# Custom_Board_2_Final.net
KiCad netlist of a schematic drawn in EAGLE
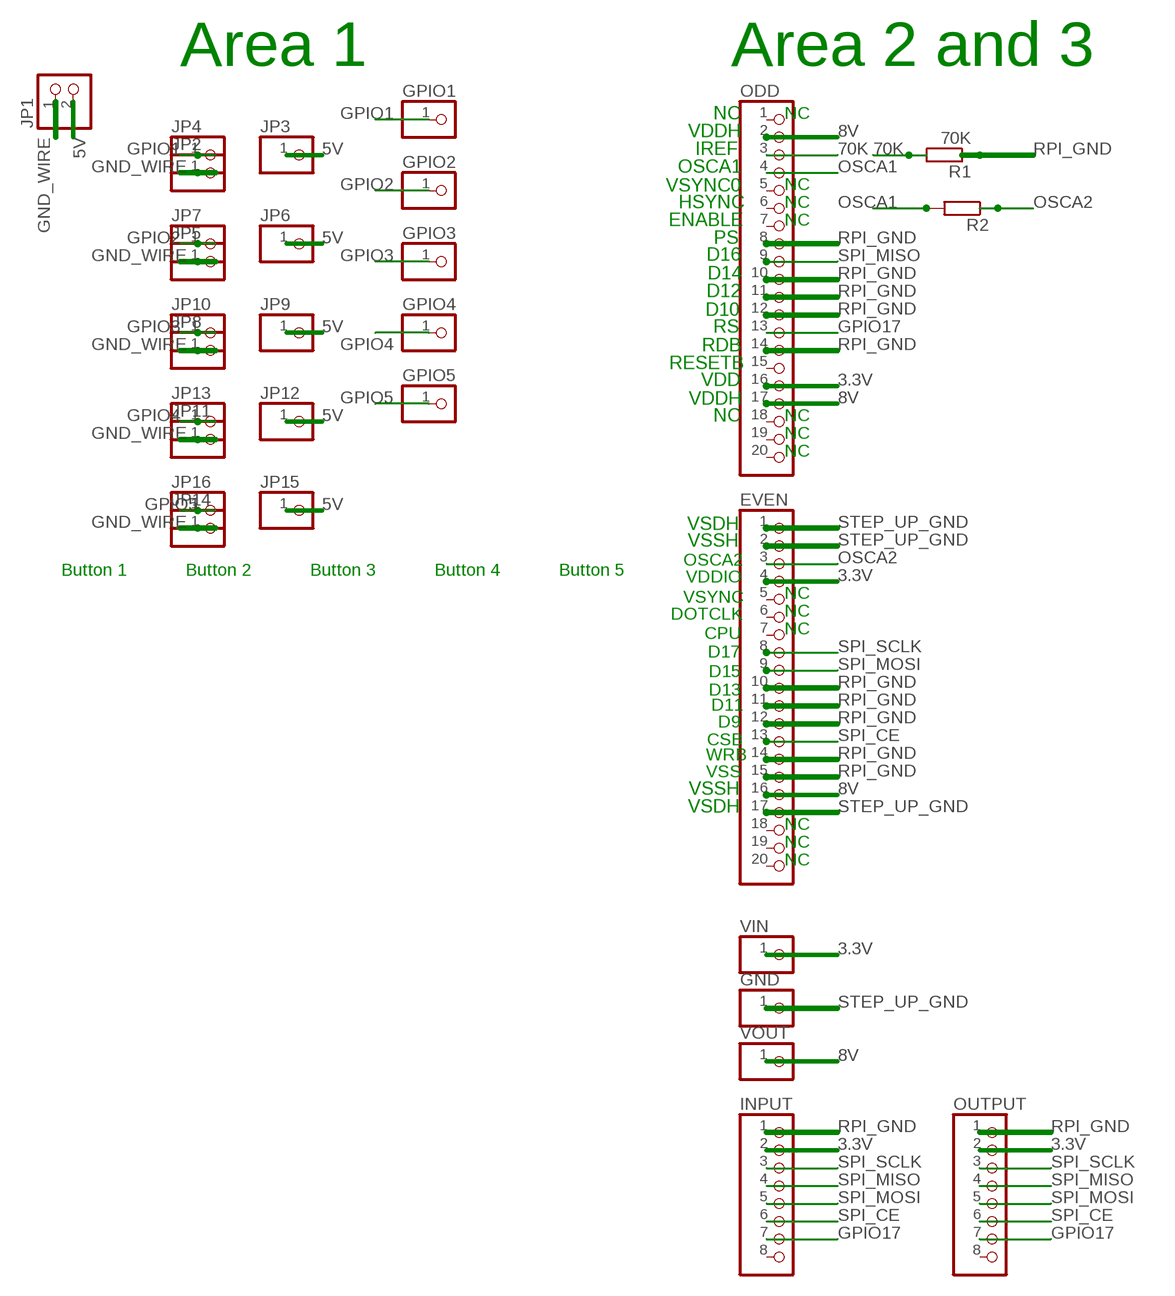
[diagram p0: schematic, sheet 1]

(export (version "E")
  (design (tool "Eeschema 10.0.6"))
  (components
    (comp (ref "EVEN")
      (value "PINHD-1X20")
      (footprint "eagle-import:1X20")
      (libsource (lib "eagle-import") (part "PINHD-1X20"))
    )
    (comp (ref "GND")
      (value "PINHD-1X1")
      (footprint "eagle-import:1X01")
      (libsource (lib "eagle-import") (part "PINHD-1X1"))
    )
    (comp (ref "GPIO1")
      (value "PINHD-1X1")
      (footprint "eagle-import:1X01")
      (libsource (lib "eagle-import") (part "PINHD-1X1"))
    )
    (comp (ref "GPIO2")
      (value "PINHD-1X1")
      (footprint "eagle-import:1X01")
      (libsource (lib "eagle-import") (part "PINHD-1X1"))
    )
    (comp (ref "GPIO3")
      (value "PINHD-1X1")
      (footprint "eagle-import:1X01")
      (libsource (lib "eagle-import") (part "PINHD-1X1"))
    )
    (comp (ref "GPIO4")
      (value "PINHD-1X1")
      (footprint "eagle-import:1X01")
      (libsource (lib "eagle-import") (part "PINHD-1X1"))
    )
    (comp (ref "GPIO5")
      (value "PINHD-1X1")
      (footprint "eagle-import:1X01")
      (libsource (lib "eagle-import") (part "PINHD-1X1"))
    )
    (comp (ref "INPUT")
      (value "PINHD-1X8")
      (footprint "eagle-import:1X08")
      (libsource (lib "eagle-import") (part "PINHD-1X8"))
    )
    (comp (ref "JP1")
      (value "PINHD-1X2")
      (footprint "eagle-import:1X02")
      (libsource (lib "eagle-import") (part "PINHD-1X2"))
    )
    (comp (ref "JP2")
      (value "PINHD-1X1")
      (footprint "eagle-import:1X01")
      (libsource (lib "eagle-import") (part "PINHD-1X1"))
    )
    (comp (ref "JP3")
      (value "PINHD-1X1")
      (footprint "eagle-import:1X01")
      (libsource (lib "eagle-import") (part "PINHD-1X1"))
    )
    (comp (ref "JP4")
      (value "PINHD-1X1")
      (footprint "eagle-import:1X01")
      (libsource (lib "eagle-import") (part "PINHD-1X1"))
    )
    (comp (ref "JP5")
      (value "PINHD-1X1")
      (footprint "eagle-import:1X01")
      (libsource (lib "eagle-import") (part "PINHD-1X1"))
    )
    (comp (ref "JP6")
      (value "PINHD-1X1")
      (footprint "eagle-import:1X01")
      (libsource (lib "eagle-import") (part "PINHD-1X1"))
    )
    (comp (ref "JP7")
      (value "PINHD-1X1")
      (footprint "eagle-import:1X01")
      (libsource (lib "eagle-import") (part "PINHD-1X1"))
    )
    (comp (ref "JP8")
      (value "PINHD-1X1")
      (footprint "eagle-import:1X01")
      (libsource (lib "eagle-import") (part "PINHD-1X1"))
    )
    (comp (ref "JP9")
      (value "PINHD-1X1")
      (footprint "eagle-import:1X01")
      (libsource (lib "eagle-import") (part "PINHD-1X1"))
    )
    (comp (ref "JP10")
      (value "PINHD-1X1")
      (footprint "eagle-import:1X01")
      (libsource (lib "eagle-import") (part "PINHD-1X1"))
    )
    (comp (ref "JP11")
      (value "PINHD-1X1")
      (footprint "eagle-import:1X01")
      (libsource (lib "eagle-import") (part "PINHD-1X1"))
    )
    (comp (ref "JP12")
      (value "PINHD-1X1")
      (footprint "eagle-import:1X01")
      (libsource (lib "eagle-import") (part "PINHD-1X1"))
    )
    (comp (ref "JP13")
      (value "PINHD-1X1")
      (footprint "eagle-import:1X01")
      (libsource (lib "eagle-import") (part "PINHD-1X1"))
    )
    (comp (ref "JP14")
      (value "PINHD-1X1")
      (footprint "eagle-import:1X01")
      (libsource (lib "eagle-import") (part "PINHD-1X1"))
    )
    (comp (ref "JP15")
      (value "PINHD-1X1")
      (footprint "eagle-import:1X01")
      (libsource (lib "eagle-import") (part "PINHD-1X1"))
    )
    (comp (ref "JP16")
      (value "PINHD-1X1")
      (footprint "eagle-import:1X01")
      (libsource (lib "eagle-import") (part "PINHD-1X1"))
    )
    (comp (ref "ODD")
      (value "PINHD-1X20")
      (footprint "eagle-import:1X20")
      (libsource (lib "eagle-import") (part "PINHD-1X20"))
    )
    (comp (ref "OUTPUT")
      (value "PINHD-1X8")
      (footprint "eagle-import:1X08")
      (libsource (lib "eagle-import") (part "PINHD-1X8"))
    )
    (comp (ref "R1")
      (value "70K")
      (footprint "eagle-import:0204_7")
      (libsource (lib "eagle-import") (part "R-EU_0204/7"))
    )
    (comp (ref "R2")
      (value "R-EU_0204/7")
      (footprint "eagle-import:0204_7")
      (libsource (lib "eagle-import") (part "R-EU_0204/7"))
    )
    (comp (ref "VIN")
      (value "PINHD-1X1")
      (footprint "eagle-import:1X01")
      (libsource (lib "eagle-import") (part "PINHD-1X1"))
    )
    (comp (ref "VOUT")
      (value "PINHD-1X1")
      (footprint "eagle-import:1X01")
      (libsource (lib "eagle-import") (part "PINHD-1X1"))
    )
  )
  (nets
    (net (code "1") (name "/3.3V") (class "Default")
      (node (ref "EVEN") (pin "4") (pinfunction "4_4") (pintype "passive"))
      (node (ref "INPUT") (pin "2") (pinfunction "2_2") (pintype "passive"))
      (node (ref "ODD") (pin "16") (pinfunction "16_16") (pintype "passive"))
      (node (ref "OUTPUT") (pin "2") (pinfunction "2_2") (pintype "passive"))
      (node (ref "VIN") (pin "1") (pinfunction "1_1") (pintype "passive"))
    )
    (net (code "2") (name "/5V") (class "Default")
      (node (ref "JP1") (pin "2") (pinfunction "2_2") (pintype "passive"))
      (node (ref "JP12") (pin "1") (pinfunction "1_1") (pintype "passive"))
      (node (ref "JP15") (pin "1") (pinfunction "1_1") (pintype "passive"))
      (node (ref "JP3") (pin "1") (pinfunction "1_1") (pintype "passive"))
      (node (ref "JP6") (pin "1") (pinfunction "1_1") (pintype "passive"))
      (node (ref "JP9") (pin "1") (pinfunction "1_1") (pintype "passive"))
    )
    (net (code "3") (name "/8V") (class "Default")
      (node (ref "EVEN") (pin "16") (pinfunction "16_16") (pintype "passive"))
      (node (ref "ODD") (pin "17") (pinfunction "17_17") (pintype "passive"))
      (node (ref "ODD") (pin "2") (pinfunction "2_2") (pintype "passive"))
      (node (ref "VOUT") (pin "1") (pinfunction "1_1") (pintype "passive"))
    )
    (net (code "4") (name "/70K") (class "Default")
      (node (ref "ODD") (pin "3") (pinfunction "3_3") (pintype "passive"))
      (node (ref "R1") (pin "2") (pinfunction "2_2") (pintype "passive"))
    )
    (net (code "5") (name "/GND_WIRE") (class "Default")
      (node (ref "JP1") (pin "1") (pinfunction "1_1") (pintype "passive"))
      (node (ref "JP11") (pin "1") (pinfunction "1_1") (pintype "passive"))
      (node (ref "JP14") (pin "1") (pinfunction "1_1") (pintype "passive"))
      (node (ref "JP2") (pin "1") (pinfunction "1_1") (pintype "passive"))
      (node (ref "JP5") (pin "1") (pinfunction "1_1") (pintype "passive"))
      (node (ref "JP8") (pin "1") (pinfunction "1_1") (pintype "passive"))
    )
    (net (code "6") (name "/GPIO1") (class "Default")
      (node (ref "GPIO1") (pin "1") (pinfunction "1_1") (pintype "passive"))
      (node (ref "JP4") (pin "1") (pinfunction "1_1") (pintype "passive"))
    )
    (net (code "7") (name "/GPIO2") (class "Default")
      (node (ref "GPIO2") (pin "1") (pinfunction "1_1") (pintype "passive"))
      (node (ref "JP7") (pin "1") (pinfunction "1_1") (pintype "passive"))
    )
    (net (code "8") (name "/GPIO3") (class "Default")
      (node (ref "GPIO3") (pin "1") (pinfunction "1_1") (pintype "passive"))
      (node (ref "JP10") (pin "1") (pinfunction "1_1") (pintype "passive"))
    )
    (net (code "9") (name "/GPIO4") (class "Default")
      (node (ref "GPIO4") (pin "1") (pinfunction "1_1") (pintype "passive"))
      (node (ref "JP13") (pin "1") (pinfunction "1_1") (pintype "passive"))
    )
    (net (code "10") (name "/GPIO5") (class "Default")
      (node (ref "GPIO5") (pin "1") (pinfunction "1_1") (pintype "passive"))
      (node (ref "JP16") (pin "1") (pinfunction "1_1") (pintype "passive"))
    )
    (net (code "11") (name "/GPIO17") (class "Default")
      (node (ref "INPUT") (pin "7") (pinfunction "7_7") (pintype "passive"))
      (node (ref "ODD") (pin "13") (pinfunction "13_13") (pintype "passive"))
      (node (ref "OUTPUT") (pin "7") (pinfunction "7_7") (pintype "passive"))
    )
    (net (code "12") (name "/OSCA1") (class "Default")
      (node (ref "ODD") (pin "4") (pinfunction "4_4") (pintype "passive"))
      (node (ref "R2") (pin "2") (pinfunction "2_2") (pintype "passive"))
    )
    (net (code "13") (name "/OSCA2") (class "Default")
      (node (ref "EVEN") (pin "3") (pinfunction "3_3") (pintype "passive"))
      (node (ref "R2") (pin "1") (pinfunction "1_1") (pintype "passive"))
    )
    (net (code "14") (name "/RPI_GND") (class "Default")
      (node (ref "EVEN") (pin "10") (pinfunction "10_10") (pintype "passive"))
      (node (ref "EVEN") (pin "11") (pinfunction "11_11") (pintype "passive"))
      (node (ref "EVEN") (pin "12") (pinfunction "12_12") (pintype "passive"))
      (node (ref "EVEN") (pin "14") (pinfunction "14_14") (pintype "passive"))
      (node (ref "EVEN") (pin "15") (pinfunction "15_15") (pintype "passive"))
      (node (ref "INPUT") (pin "1") (pinfunction "1_1") (pintype "passive"))
      (node (ref "ODD") (pin "10") (pinfunction "10_10") (pintype "passive"))
      (node (ref "ODD") (pin "11") (pinfunction "11_11") (pintype "passive"))
      (node (ref "ODD") (pin "12") (pinfunction "12_12") (pintype "passive"))
      (node (ref "ODD") (pin "14") (pinfunction "14_14") (pintype "passive"))
      (node (ref "ODD") (pin "8") (pinfunction "8_8") (pintype "passive"))
      (node (ref "OUTPUT") (pin "1") (pinfunction "1_1") (pintype "passive"))
      (node (ref "R1") (pin "1") (pinfunction "1_1") (pintype "passive"))
    )
    (net (code "15") (name "/SPI_CE") (class "Default")
      (node (ref "EVEN") (pin "13") (pinfunction "13_13") (pintype "passive"))
      (node (ref "INPUT") (pin "6") (pinfunction "6_6") (pintype "passive"))
      (node (ref "OUTPUT") (pin "6") (pinfunction "6_6") (pintype "passive"))
    )
    (net (code "16") (name "/SPI_MISO") (class "Default")
      (node (ref "INPUT") (pin "4") (pinfunction "4_4") (pintype "passive"))
      (node (ref "ODD") (pin "9") (pinfunction "9_9") (pintype "passive"))
      (node (ref "OUTPUT") (pin "4") (pinfunction "4_4") (pintype "passive"))
    )
    (net (code "17") (name "/SPI_MOSI") (class "Default")
      (node (ref "EVEN") (pin "9") (pinfunction "9_9") (pintype "passive"))
      (node (ref "INPUT") (pin "5") (pinfunction "5_5") (pintype "passive"))
      (node (ref "OUTPUT") (pin "5") (pinfunction "5_5") (pintype "passive"))
    )
    (net (code "18") (name "/SPI_SCLK") (class "Default")
      (node (ref "EVEN") (pin "8") (pinfunction "8_8") (pintype "passive"))
      (node (ref "INPUT") (pin "3") (pinfunction "3_3") (pintype "passive"))
      (node (ref "OUTPUT") (pin "3") (pinfunction "3_3") (pintype "passive"))
    )
    (net (code "19") (name "/STEP_UP_GND") (class "Default")
      (node (ref "EVEN") (pin "1") (pinfunction "1_1") (pintype "passive"))
      (node (ref "EVEN") (pin "17") (pinfunction "17_17") (pintype "passive"))
      (node (ref "EVEN") (pin "2") (pinfunction "2_2") (pintype "passive"))
      (node (ref "GND") (pin "1") (pinfunction "1_1") (pintype "passive"))
    )
    (net (code "20") (name "unconnected-(EVEN-Pad5)") (class "Default")
      (node (ref "EVEN") (pin "5") (pinfunction "5_5") (pintype "passive"))
    )
    (net (code "21") (name "unconnected-(EVEN-Pad6)") (class "Default")
      (node (ref "EVEN") (pin "6") (pinfunction "6_6") (pintype "passive"))
    )
    (net (code "22") (name "unconnected-(EVEN-Pad7)") (class "Default")
      (node (ref "EVEN") (pin "7") (pinfunction "7_7") (pintype "passive"))
    )
    (net (code "23") (name "unconnected-(EVEN-Pad18)") (class "Default")
      (node (ref "EVEN") (pin "18") (pinfunction "18_18") (pintype "passive"))
    )
    (net (code "24") (name "unconnected-(EVEN-Pad19)") (class "Default")
      (node (ref "EVEN") (pin "19") (pinfunction "19_19") (pintype "passive"))
    )
    (net (code "25") (name "unconnected-(EVEN-Pad20)") (class "Default")
      (node (ref "EVEN") (pin "20") (pinfunction "20_20") (pintype "passive"))
    )
    (net (code "26") (name "unconnected-(INPUT-Pad8)") (class "Default")
      (node (ref "INPUT") (pin "8") (pinfunction "8_8") (pintype "passive"))
    )
    (net (code "27") (name "unconnected-(ODD-Pad1)") (class "Default")
      (node (ref "ODD") (pin "1") (pinfunction "1_1") (pintype "passive"))
    )
    (net (code "28") (name "unconnected-(ODD-Pad5)") (class "Default")
      (node (ref "ODD") (pin "5") (pinfunction "5_5") (pintype "passive"))
    )
    (net (code "29") (name "unconnected-(ODD-Pad6)") (class "Default")
      (node (ref "ODD") (pin "6") (pinfunction "6_6") (pintype "passive"))
    )
    (net (code "30") (name "unconnected-(ODD-Pad7)") (class "Default")
      (node (ref "ODD") (pin "7") (pinfunction "7_7") (pintype "passive"))
    )
    (net (code "31") (name "unconnected-(ODD-Pad15)") (class "Default")
      (node (ref "ODD") (pin "15") (pinfunction "15_15") (pintype "passive"))
    )
    (net (code "32") (name "unconnected-(ODD-Pad18)") (class "Default")
      (node (ref "ODD") (pin "18") (pinfunction "18_18") (pintype "passive"))
    )
    (net (code "33") (name "unconnected-(ODD-Pad19)") (class "Default")
      (node (ref "ODD") (pin "19") (pinfunction "19_19") (pintype "passive"))
    )
    (net (code "34") (name "unconnected-(ODD-Pad20)") (class "Default")
      (node (ref "ODD") (pin "20") (pinfunction "20_20") (pintype "passive"))
    )
    (net (code "35") (name "unconnected-(OUTPUT-Pad8)") (class "Default")
      (node (ref "OUTPUT") (pin "8") (pinfunction "8_8") (pintype "passive"))
    )
  )
)
